# Sheet1.net
KiCad netlist of a schematic drawn in Altium Designer
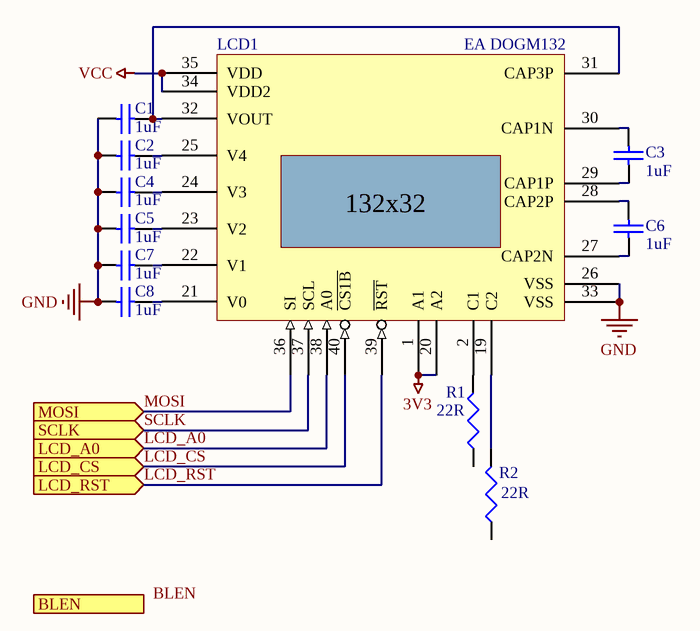
[diagram p0: Sheet1.SchDoc]

(export (version "E")
  (design (tool "Eeschema 10.0.6"))
  (components
    (comp (ref "C1")
      (value "1uF")
      (footprint "1608[0603]")
      (description "Capacitor (Semiconductor SIM Model)")
      (fields (field (name "Comment") "Cap Semi") (field (name "PUBLISHER") "Altium Limited"))
      (libsource (lib "Miscellaneous Devices") (part "Cap Semi"))
    )
    (comp (ref "C2")
      (value "1uF")
      (footprint "1608[0603]")
      (description "Capacitor (Semiconductor SIM Model)")
      (fields (field (name "Comment") "Cap Semi") (field (name "PUBLISHER") "Altium Limited"))
      (libsource (lib "Miscellaneous Devices") (part "Cap Semi"))
    )
    (comp (ref "C3")
      (value "1uF")
      (footprint "1608[0603]")
      (description "Capacitor (Semiconductor SIM Model)")
      (fields (field (name "Comment") "Cap Semi") (field (name "PUBLISHER") "Altium Limited"))
      (libsource (lib "Miscellaneous Devices") (part "Cap Semi"))
    )
    (comp (ref "C4")
      (value "1uF")
      (footprint "1608[0603]")
      (description "Capacitor (Semiconductor SIM Model)")
      (fields (field (name "Comment") "Cap Semi") (field (name "PUBLISHER") "Altium Limited"))
      (libsource (lib "Miscellaneous Devices") (part "Cap Semi"))
    )
    (comp (ref "C5")
      (value "1uF")
      (footprint "1608[0603]")
      (description "Capacitor (Semiconductor SIM Model)")
      (fields (field (name "Comment") "Cap Semi") (field (name "PUBLISHER") "Altium Limited"))
      (libsource (lib "Miscellaneous Devices") (part "Cap Semi"))
    )
    (comp (ref "C6")
      (value "1uF")
      (footprint "1608[0603]")
      (description "Capacitor (Semiconductor SIM Model)")
      (fields (field (name "Comment") "Cap Semi") (field (name "PUBLISHER") "Altium Limited"))
      (libsource (lib "Miscellaneous Devices") (part "Cap Semi"))
    )
    (comp (ref "C7")
      (value "1uF")
      (footprint "1608[0603]")
      (description "Capacitor (Semiconductor SIM Model)")
      (fields (field (name "Comment") "Cap Semi") (field (name "PUBLISHER") "Altium Limited"))
      (libsource (lib "Miscellaneous Devices") (part "Cap Semi"))
    )
    (comp (ref "C8")
      (value "1uF")
      (footprint "1608[0603]")
      (description "Capacitor (Semiconductor SIM Model)")
      (fields (field (name "Comment") "Cap Semi") (field (name "PUBLISHER") "Altium Limited"))
      (libsource (lib "Miscellaneous Devices") (part "Cap Semi"))
    )
    (comp (ref "LCD1")
      (value "EA DOGM132")
      (footprint "EA DOGM132-5")
      (description "132x32 graphical LCD")
      (libsource (lib "6DOF IMU_ver1") (part "EA DOGM132"))
    )
    (comp (ref "R1")
      (value "22R")
      (footprint "J1-0603")
      (description "Resistor")
      (fields (field (name "Comment") "Res3") (field (name "PUBLISHER") "Altium Limited"))
      (libsource (lib "Miscellaneous Devices") (part "Res3"))
    )
    (comp (ref "R2")
      (value "22R")
      (footprint "J1-0603")
      (description "Resistor")
      (fields (field (name "Comment") "Res3") (field (name "PUBLISHER") "Altium Limited"))
      (libsource (lib "Miscellaneous Devices") (part "Res3"))
    )
  )
  (nets
    (net (code "2") (name "/LCD_A0") (class "Default")
      (node (ref "LCD1") (pin "38") (pinfunction "A0_38") (pintype "input"))
    )
    (net (code "3") (name "/LCD_CS") (class "Default")
      (node (ref "LCD1") (pin "40") (pinfunction "~{CS1B}_40") (pintype "input"))
    )
    (net (code "4") (name "/LCD_RST") (class "Default")
      (node (ref "LCD1") (pin "39") (pinfunction "~{RST}_39") (pintype "input"))
    )
    (net (code "5") (name "/MOSI") (class "Default")
      (node (ref "LCD1") (pin "36") (pinfunction "SI_36") (pintype "input"))
    )
    (net (code "6") (name "/SCLK") (class "Default")
      (node (ref "LCD1") (pin "37") (pinfunction "SCL_37") (pintype "input"))
    )
    (net (code "7") (name "3V3") (class "Default")
      (node (ref "LCD1") (pin "1") (pinfunction "A1_1") (pintype "passive"))
      (node (ref "LCD1") (pin "20") (pinfunction "A2_20") (pintype "passive"))
    )
    (net (code "8") (name "GND") (class "Default")
      (node (ref "C1") (pin "1") (pinfunction "1_1") (pintype "passive"))
      (node (ref "C2") (pin "1") (pinfunction "1_1") (pintype "passive"))
      (node (ref "C4") (pin "1") (pinfunction "1_1") (pintype "passive"))
      (node (ref "C5") (pin "1") (pinfunction "1_1") (pintype "passive"))
      (node (ref "C7") (pin "1") (pinfunction "1_1") (pintype "passive"))
      (node (ref "C8") (pin "1") (pinfunction "1_1") (pintype "passive"))
      (node (ref "LCD1") (pin "26") (pinfunction "VSS_26") (pintype "passive"))
      (node (ref "LCD1") (pin "33") (pinfunction "VSS_33") (pintype "passive"))
    )
    (net (code "9") (name "Net-(LCD1-C1)") (class "Default")
      (node (ref "LCD1") (pin "2") (pinfunction "C1_2") (pintype "passive"))
      (node (ref "R1") (pin "2") (pinfunction "2_2") (pintype "passive"))
    )
    (net (code "10") (name "Net-(LCD1-C2)") (class "Default")
      (node (ref "LCD1") (pin "19") (pinfunction "C2_19") (pintype "passive"))
      (node (ref "R2") (pin "2") (pinfunction "2_2") (pintype "passive"))
    )
    (net (code "11") (name "Net-(LCD1-CAP1N)") (class "Default")
      (node (ref "C3") (pin "1") (pinfunction "1_1") (pintype "passive"))
      (node (ref "LCD1") (pin "30") (pinfunction "CAP1N_30") (pintype "passive"))
    )
    (net (code "12") (name "Net-(LCD1-CAP1P)") (class "Default")
      (node (ref "C3") (pin "2") (pinfunction "2_2") (pintype "passive"))
      (node (ref "LCD1") (pin "29") (pinfunction "CAP1P_29") (pintype "passive"))
    )
    (net (code "13") (name "Net-(LCD1-CAP2N)") (class "Default")
      (node (ref "C6") (pin "2") (pinfunction "2_2") (pintype "passive"))
      (node (ref "LCD1") (pin "27") (pinfunction "CAP2N_27") (pintype "passive"))
    )
    (net (code "14") (name "Net-(LCD1-CAP2P)") (class "Default")
      (node (ref "C6") (pin "1") (pinfunction "1_1") (pintype "passive"))
      (node (ref "LCD1") (pin "28") (pinfunction "CAP2P_28") (pintype "passive"))
    )
    (net (code "15") (name "Net-(LCD1-CAP3P)") (class "Default")
      (node (ref "C1") (pin "2") (pinfunction "2_2") (pintype "passive"))
      (node (ref "LCD1") (pin "31") (pinfunction "CAP3P_31") (pintype "passive"))
      (node (ref "LCD1") (pin "32") (pinfunction "VOUT_32") (pintype "passive"))
    )
    (net (code "16") (name "Net-(LCD1-V0)") (class "Default")
      (node (ref "C8") (pin "2") (pinfunction "2_2") (pintype "passive"))
      (node (ref "LCD1") (pin "21") (pinfunction "V0_21") (pintype "passive"))
    )
    (net (code "17") (name "Net-(LCD1-V1)") (class "Default")
      (node (ref "C7") (pin "2") (pinfunction "2_2") (pintype "passive"))
      (node (ref "LCD1") (pin "22") (pinfunction "V1_22") (pintype "passive"))
    )
    (net (code "18") (name "Net-(LCD1-V2)") (class "Default")
      (node (ref "C5") (pin "2") (pinfunction "2_2") (pintype "passive"))
      (node (ref "LCD1") (pin "23") (pinfunction "V2_23") (pintype "passive"))
    )
    (net (code "19") (name "Net-(LCD1-V3)") (class "Default")
      (node (ref "C4") (pin "2") (pinfunction "2_2") (pintype "passive"))
      (node (ref "LCD1") (pin "24") (pinfunction "V3_24") (pintype "passive"))
    )
    (net (code "20") (name "Net-(LCD1-V4)") (class "Default")
      (node (ref "C2") (pin "2") (pinfunction "2_2") (pintype "passive"))
      (node (ref "LCD1") (pin "25") (pinfunction "V4_25") (pintype "passive"))
    )
    (net (code "21") (name "VCC") (class "Default")
      (node (ref "LCD1") (pin "34") (pinfunction "VDD2_34") (pintype "passive"))
      (node (ref "LCD1") (pin "35") (pinfunction "VDD_35") (pintype "passive"))
    )
    (net (code "22") (name "unconnected-(R1-Pad1)") (class "Default")
      (node (ref "R1") (pin "1") (pinfunction "1_1") (pintype "passive"))
    )
    (net (code "23") (name "unconnected-(R2-Pad1)") (class "Default")
      (node (ref "R2") (pin "1") (pinfunction "1_1") (pintype "passive"))
    )
  )
)
